# PCB.net
KiCad netlist of a schematic drawn in Altium Designer
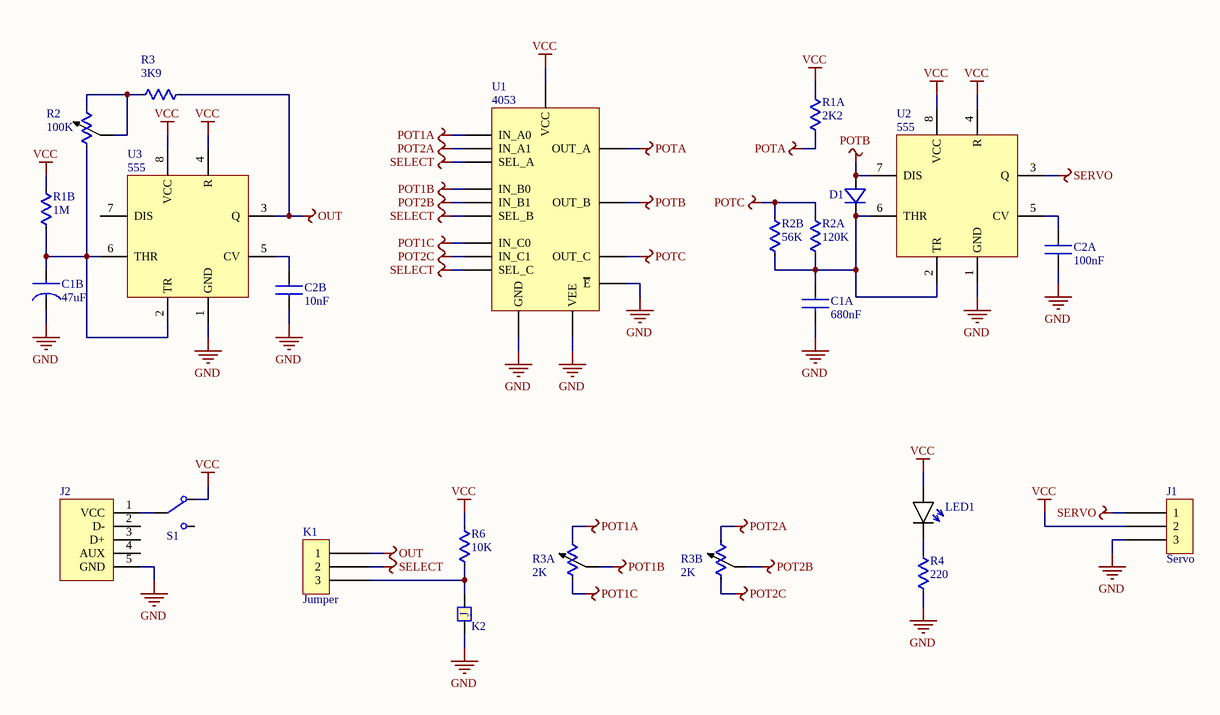
[diagram p0: PCB.SchDoc]

(export (version "E")
  (design (tool "Eeschema 10.0.6"))
  (components
    (comp (ref "C1A")
      (value "680nF")
      (footprint "CAP_POL_20MM")
      (fields (field (name "Comment") "CAP-CER"))
      (libsource (lib "AltiumLibrary") (part "CAP-CER"))
    )
    (comp (ref "C1B")
      (value "47uF")
      (footprint "CAP-ELEC-5x11x2mm")
      (fields (field (name "Comment") "CAP-ELEC"))
      (libsource (lib "AltiumLibrary") (part "CAP-ELEC"))
    )
    (comp (ref "C2A")
      (value "100nF")
      (footprint "CAP-CER")
      (fields (field (name "Comment") "CAP-CER"))
      (libsource (lib "AltiumLibrary") (part "CAP-CER"))
    )
    (comp (ref "C2B")
      (value "10nF")
      (footprint "CAP-CER")
      (fields (field (name "Comment") "CAP-CER"))
      (libsource (lib "AltiumLibrary") (part "CAP-CER"))
    )
    (comp (ref "D1") (value "DIODE") (footprint "DO-41") (libsource (lib "AltiumLibrary") (part "DIODE")))
    (comp (ref "J1") (value "Servo") (footprint "Header 1x3") (libsource (lib "") (part "Header 1x3_1")))
    (comp (ref "J2")
      (value "MINI USB")
      (footprint "5075BMR-05")
      (libsource (lib "AltiumLibrary") (part "MINI USB"))
    )
    (comp (ref "K1")
      (value "Jumper")
      (footprint "Header 1x3")
      (libsource (lib "AltiumLibrary") (part "Header 1x3"))
    )
    (comp (ref "K2") (value "JUMPER") (footprint "JUMPER") (libsource (lib "AltiumLibrary") (part "JUMPER")))
    (comp (ref "LED1")
      (value "LED")
      (footprint "LED-3MM-GREEN")
      (libsource (lib "AltiumLibrary") (part "LED"))
    )
    (comp (ref "R1A")
      (value "2K2")
      (footprint "RES-Axial-400mil")
      (fields (field (name "Comment") "RES"))
      (libsource (lib "AltiumLibrary") (part "RES"))
    )
    (comp (ref "R1B")
      (value "1M")
      (footprint "RES-Axial-400mil")
      (fields (field (name "Comment") "RES"))
      (libsource (lib "AltiumLibrary") (part "RES"))
    )
    (comp (ref "R2")
      (value "100K")
      (footprint "TRIMPOT")
      (fields (field (name "Comment") "POT"))
      (libsource (lib "AltiumLibrary") (part "POT"))
    )
    (comp (ref "R2A")
      (value "120K")
      (footprint "RES-Axial-400mil")
      (fields (field (name "Comment") "RES"))
      (libsource (lib "AltiumLibrary") (part "RES"))
    )
    (comp (ref "R2B")
      (value "56K")
      (footprint "RES-Axial-400mil")
      (fields (field (name "Comment") "RES"))
      (libsource (lib "AltiumLibrary") (part "RES"))
    )
    (comp (ref "R3")
      (value "3K9")
      (footprint "RES-Axial-400mil")
      (fields (field (name "Comment") "RES"))
      (libsource (lib "") (part "RES_1"))
    )
    (comp (ref "R3A")
      (value "2K")
      (footprint "TRIMPOT")
      (fields (field (name "Comment") "POT"))
      (libsource (lib "AltiumLibrary") (part "POT"))
    )
    (comp (ref "R3B")
      (value "2K")
      (footprint "TRIMPOT")
      (fields (field (name "Comment") "POT"))
      (libsource (lib "AltiumLibrary") (part "POT"))
    )
    (comp (ref "R4")
      (value "220")
      (footprint "RES-Axial-400mil")
      (fields (field (name "Comment") "RES"))
      (libsource (lib "") (part "RES_2"))
    )
    (comp (ref "R6")
      (value "10K")
      (footprint "RES-Axial-400mil")
      (fields (field (name "Comment") "RES"))
      (libsource (lib "AltiumLibrary") (part "RES"))
    )
    (comp (ref "S1")
      (value "SLIDE-SWITCH")
      (footprint "SWITCH")
      (libsource (lib "AltiumLibrary") (part "SLIDE-SWITCH"))
    )
    (comp (ref "U1") (value "4053") (footprint "DIP16") (libsource (lib "AltiumLibrary") (part "4053")))
    (comp (ref "U2") (value "555") (footprint "DIP8") (libsource (lib "AltiumLibrary") (part "555")))
    (comp (ref "U3") (value "555") (footprint "DIP8") (libsource (lib "AltiumLibrary") (part "555")))
  )
  (nets
    (net (code "1") (name "GND") (class "Default")
      (node (ref "C1A") (pin "1") (pintype "passive"))
      (node (ref "C1B") (pin "2") (pintype "passive"))
      (node (ref "C2A") (pin "1") (pintype "passive"))
      (node (ref "C2B") (pin "2") (pintype "passive"))
      (node (ref "J1") (pin "3") (pinfunction "3_3") (pintype "passive"))
      (node (ref "J2") (pin "5") (pinfunction "GND_5") (pintype "passive"))
      (node (ref "K2") (pin "2") (pintype "passive"))
      (node (ref "R4") (pin "2") (pintype "passive"))
      (node (ref "U1") (pin "6") (pinfunction "E_6") (pintype "passive"))
      (node (ref "U1") (pin "7") (pinfunction "VEE_7") (pintype "passive"))
      (node (ref "U1") (pin "8") (pinfunction "GND_8") (pintype "passive"))
      (node (ref "U2") (pin "1") (pinfunction "GND_1") (pintype "passive"))
      (node (ref "U3") (pin "1") (pinfunction "GND_1") (pintype "passive"))
    )
    (net (code "2") (name "Net-(J2-VCC)") (class "Default")
      (node (ref "J2") (pin "1") (pinfunction "VCC_1") (pintype "passive"))
      (node (ref "S1") (pin "2") (pintype "power_in"))
    )
    (net (code "3") (name "Net-(K1-Pad3)") (class "Default")
      (node (ref "K1") (pin "3") (pinfunction "3_3") (pintype "passive"))
      (node (ref "K2") (pin "1") (pintype "passive"))
      (node (ref "R6") (pin "1") (pintype "passive"))
    )
    (net (code "4") (name "Net-(LED1-PadK)") (class "Default")
      (node (ref "LED1") (pin "K") (pintype "passive"))
      (node (ref "R4") (pin "1") (pintype "passive"))
    )
    (net (code "5") (name "Net-(R2-Pad1)") (class "Default")
      (node (ref "R2") (pin "1") (pintype "passive"))
      (node (ref "R2") (pin "2") (pintype "passive"))
      (node (ref "R3") (pin "1") (pintype "passive"))
    )
    (net (code "6") (name "Net-(U2-CV)") (class "Default")
      (node (ref "C2A") (pin "2") (pintype "passive"))
      (node (ref "U2") (pin "5") (pinfunction "CV_5") (pintype "passive"))
    )
    (net (code "7") (name "Net-(U2-THR)") (class "Default")
      (node (ref "C1A") (pin "2") (pintype "passive"))
      (node (ref "D1") (pin "K") (pintype "passive"))
      (node (ref "R2A") (pin "1") (pintype "passive"))
      (node (ref "R2B") (pin "1") (pintype "passive"))
      (node (ref "U2") (pin "2") (pinfunction "TR_2") (pintype "passive"))
      (node (ref "U2") (pin "6") (pinfunction "THR_6") (pintype "passive"))
    )
    (net (code "8") (name "Net-(U3-CV)") (class "Default")
      (node (ref "C2B") (pin "1") (pintype "passive"))
      (node (ref "U3") (pin "5") (pinfunction "CV_5") (pintype "passive"))
    )
    (net (code "9") (name "Net-(U3-THR)") (class "Default")
      (node (ref "C1B") (pin "1") (pintype "passive"))
      (node (ref "R1B") (pin "1") (pintype "passive"))
      (node (ref "R2") (pin "3") (pintype "passive"))
      (node (ref "U3") (pin "2") (pinfunction "TR_2") (pintype "passive"))
      (node (ref "U3") (pin "6") (pinfunction "THR_6") (pintype "passive"))
    )
    (net (code "10") (name "OUT") (class "Default")
      (node (ref "K1") (pin "1") (pinfunction "1_1") (pintype "passive"))
      (node (ref "R3") (pin "2") (pintype "passive"))
      (node (ref "U3") (pin "3") (pinfunction "Q_3") (pintype "passive"))
    )
    (net (code "11") (name "POT1A") (class "Default")
      (node (ref "R3A") (pin "1") (pintype "passive"))
      (node (ref "U1") (pin "12") (pinfunction "IN_A0_12") (pintype "passive"))
    )
    (net (code "12") (name "POT1B") (class "Default")
      (node (ref "R3A") (pin "2") (pintype "passive"))
      (node (ref "U1") (pin "2") (pinfunction "IN_B0_2") (pintype "passive"))
    )
    (net (code "13") (name "POT1C") (class "Default")
      (node (ref "R3A") (pin "3") (pintype "passive"))
      (node (ref "U1") (pin "5") (pinfunction "IN_C0_5") (pintype "passive"))
    )
    (net (code "14") (name "POT2A") (class "Default")
      (node (ref "R3B") (pin "1") (pintype "passive"))
      (node (ref "U1") (pin "13") (pinfunction "IN_A1_13") (pintype "passive"))
    )
    (net (code "15") (name "POT2B") (class "Default")
      (node (ref "R3B") (pin "2") (pintype "passive"))
      (node (ref "U1") (pin "1") (pinfunction "IN_B1_1") (pintype "passive"))
    )
    (net (code "16") (name "POT2C") (class "Default")
      (node (ref "R3B") (pin "3") (pintype "passive"))
      (node (ref "U1") (pin "3") (pinfunction "IN_C1_3") (pintype "passive"))
    )
    (net (code "17") (name "POTA") (class "Default")
      (node (ref "R1A") (pin "1") (pintype "passive"))
      (node (ref "U1") (pin "14") (pinfunction "OUT_A_14") (pintype "passive"))
    )
    (net (code "18") (name "POTB") (class "Default")
      (node (ref "D1") (pin "A") (pintype "passive"))
      (node (ref "U1") (pin "15") (pinfunction "OUT_B_15") (pintype "passive"))
      (node (ref "U2") (pin "7") (pinfunction "DIS_7") (pintype "passive"))
    )
    (net (code "19") (name "POTC") (class "Default")
      (node (ref "R2A") (pin "2") (pintype "passive"))
      (node (ref "R2B") (pin "2") (pintype "passive"))
      (node (ref "U1") (pin "4") (pinfunction "OUT_C_4") (pintype "passive"))
    )
    (net (code "20") (name "SELECT") (class "Default")
      (node (ref "K1") (pin "2") (pinfunction "2_2") (pintype "passive"))
      (node (ref "U1") (pin "10") (pinfunction "SEL_B_10") (pintype "passive"))
      (node (ref "U1") (pin "11") (pinfunction "SEL_A_11") (pintype "passive"))
      (node (ref "U1") (pin "9") (pinfunction "SEL_C_9") (pintype "passive"))
    )
    (net (code "21") (name "SERVO") (class "Default")
      (node (ref "J1") (pin "1") (pinfunction "1_1") (pintype "passive"))
      (node (ref "U2") (pin "3") (pinfunction "Q_3") (pintype "passive"))
    )
    (net (code "22") (name "VCC") (class "Default")
      (node (ref "J1") (pin "2") (pinfunction "2_2") (pintype "passive"))
      (node (ref "LED1") (pin "A") (pintype "passive"))
      (node (ref "R1A") (pin "2") (pintype "passive"))
      (node (ref "R1B") (pin "2") (pintype "passive"))
      (node (ref "R6") (pin "2") (pintype "passive"))
      (node (ref "S1") (pin "1") (pintype "power_in"))
      (node (ref "U1") (pin "16") (pinfunction "VCC_16") (pintype "passive"))
      (node (ref "U2") (pin "4") (pinfunction "R_4") (pintype "passive"))
      (node (ref "U2") (pin "8") (pinfunction "VCC_8") (pintype "passive"))
      (node (ref "U3") (pin "4") (pinfunction "R_4") (pintype "passive"))
      (node (ref "U3") (pin "8") (pinfunction "VCC_8") (pintype "passive"))
    )
    (net (code "23") (name "unconnected-(J2-AUX-Pad4)") (class "Default")
      (node (ref "J2") (pin "4") (pinfunction "AUX_4") (pintype "passive"))
    )
    (net (code "24") (name "unconnected-(J2-D+-Pad3)") (class "Default")
      (node (ref "J2") (pin "3") (pinfunction "D+_3") (pintype "passive"))
    )
    (net (code "25") (name "unconnected-(J2-D--Pad2)") (class "Default")
      (node (ref "J2") (pin "2") (pinfunction "D-_2") (pintype "passive"))
    )
    (net (code "26") (name "unconnected-(S1-Pad3)") (class "Default")
      (node (ref "S1") (pin "3") (pintype "power_in"))
    )
    (net (code "27") (name "unconnected-(U3-DIS-Pad7)") (class "Default")
      (node (ref "U3") (pin "7") (pinfunction "DIS_7") (pintype "passive"))
    )
  )
)
